# CH340.net
KiCad netlist of a schematic drawn in Altium Designer
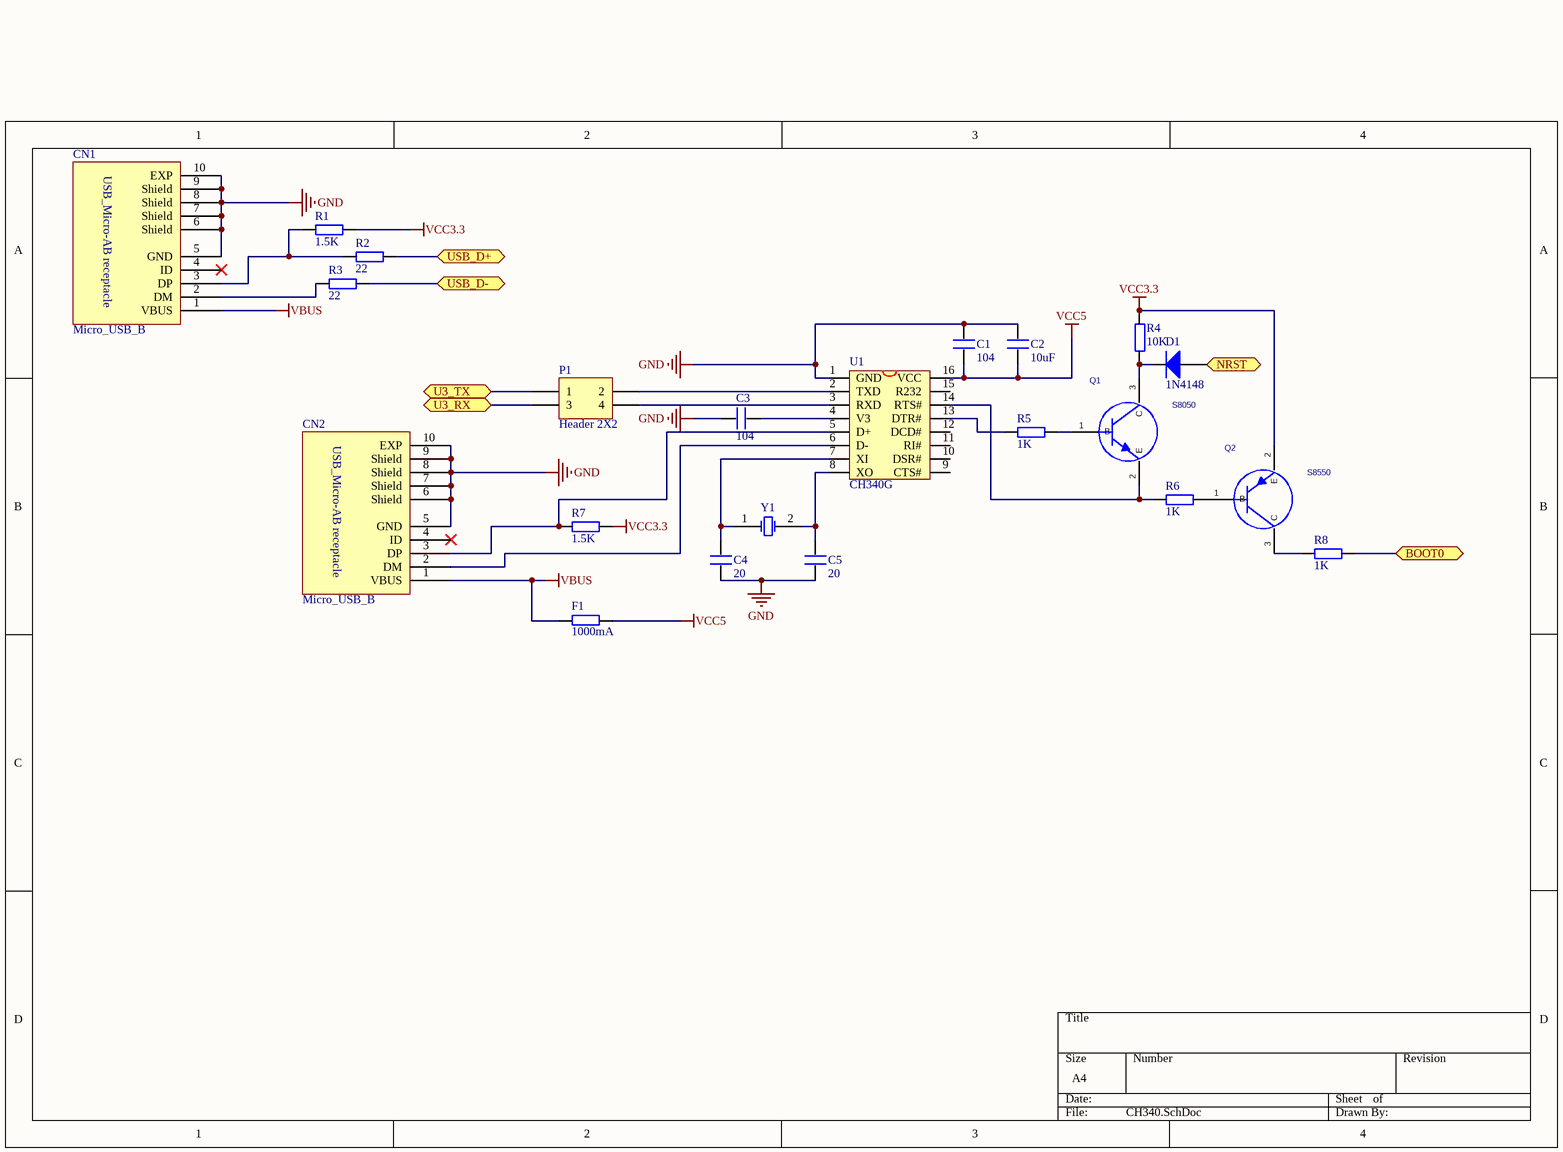
[diagram p0: CH340.SchDoc]

(export (version "E")
  (design (tool "Eeschema 10.0.6"))
  (components
    (comp (ref "C1") (value "104") (footprint "0603C") (libsource (lib "WarShip V3 STM32103封装库") (part "C")))
    (comp (ref "C2") (value "10uF") (footprint "0805C") (libsource (lib "WarShip V3 STM32103封装库") (part "C")))
    (comp (ref "C3") (value "104") (footprint "0603C") (libsource (lib "WarShip V3 STM32103封装库") (part "C")))
    (comp (ref "C4") (value "20") (footprint "0603C") (libsource (lib "WarShip V3 STM32103封装库") (part "C")))
    (comp (ref "C5") (value "20") (footprint "0603C") (libsource (lib "WarShip V3 STM32103封装库") (part "C")))
    (comp (ref "CN1")
      (value "Micro_USB_B")
      (footprint "Molex_1050170001")
      (libsource (lib "3D库") (part "Micro_USB_B"))
    )
    (comp (ref "CN2")
      (value "Micro_USB_B")
      (footprint "Molex_1050170001")
      (libsource (lib "3D库") (part "Micro_USB_B"))
    )
    (comp (ref "D1")
      (value "1N4148")
      (footprint "DIODE_SOP")
      (description "Default Diode")
      (fields (field (name "PUBLISHER") "Altium Limited"))
      (libsource (lib "3D库") (part "Diode"))
    )
    (comp (ref "F1")
      (value "1000mA")
      (footprint "0805F")
      (libsource (lib "WarShip V3 STM32103封装库") (part "R"))
    )
    (comp (ref "P1")
      (value "Header 2X2")
      (footprint "HDR2X2")
      (description "Header, 2-Pin, Dual row")
      (fields (field (name "PUBLISHER") "Altium Limited"))
      (libsource (lib "Miscellaneous Connectors") (part "Header 2X2"))
    )
    (comp (ref "Q1")
      (value "S8050")
      (footprint "SOT-23")
      (description "NPN")
      (libsource (lib "ISO-V3") (part "S8050"))
    )
    (comp (ref "Q2")
      (value "S8550")
      (footprint "SOT-23")
      (description "NPN")
      (libsource (lib "ISO-V3") (part "S8550"))
    )
    (comp (ref "R1") (value "1.5K") (footprint "0603R") (libsource (lib "Explorer STM32F407封装库") (part "R")))
    (comp (ref "R2") (value "22") (footprint "0603R") (libsource (lib "Explorer STM32F407封装库") (part "R")))
    (comp (ref "R3") (value "22") (footprint "0603R") (libsource (lib "Explorer STM32F407封装库") (part "R")))
    (comp (ref "R4") (value "10K") (footprint "0603R") (libsource (lib "Explorer STM32F407封装库") (part "R")))
    (comp (ref "R5") (value "1K") (footprint "0603R") (libsource (lib "Explorer STM32F407封装库") (part "R")))
    (comp (ref "R6") (value "1K") (footprint "0603R") (libsource (lib "Explorer STM32F407封装库") (part "R")))
    (comp (ref "R7") (value "1.5K") (footprint "0603R") (libsource (lib "Explorer STM32F407封装库") (part "R")))
    (comp (ref "R8") (value "1K") (footprint "0603R") (libsource (lib "Explorer STM32F407封装库") (part "R")))
    (comp (ref "U1")
      (value "CH340G")
      (footprint "SOP16_M")
      (description "USB2UART")
      (libsource (lib "WarShip V3 STM32103封装库") (part "CH340G"))
    )
    (comp (ref "Y1")
      (value "NX3225GD-8.000M-EXS00A-CG04874[N/A]")
      (footprint "XTAL_SMD")
      (description "Crystal Oscillator")
      (fields (field (name "PUBLISHER") "Altium Limited"))
      (libsource (lib "3D库") (part "XTAL"))
    )
  )
  (nets
    (net (code "1") (name "/BOOT0") (class "Default") (node (ref "R8") (pin "2") (pintype "passive")))
    (net (code "2") (name "/NRST") (class "Default")
      (node (ref "D1") (pin "1") (pinfunction "A_1") (pintype "passive"))
    )
    (net (code "3") (name "/U3_RX") (class "Default")
      (node (ref "P1") (pin "3") (pinfunction "3_3") (pintype "passive"))
    )
    (net (code "4") (name "/U3_TX") (class "Default")
      (node (ref "P1") (pin "1") (pinfunction "1_1") (pintype "passive"))
    )
    (net (code "5") (name "/USB_D+") (class "Default") (node (ref "R2") (pin "2") (pintype "passive")))
    (net (code "6") (name "/USB_D-") (class "Default") (node (ref "R3") (pin "2") (pintype "passive")))
    (net (code "7") (name "GND") (class "Default")
      (node (ref "C1") (pin "2") (pintype "passive"))
      (node (ref "C2") (pin "2") (pintype "passive"))
      (node (ref "C3") (pin "2") (pintype "passive"))
      (node (ref "C4") (pin "1") (pintype "passive"))
      (node (ref "C5") (pin "1") (pintype "passive"))
      (node (ref "CN1") (pin "10") (pinfunction "EXP_10") (pintype "passive"))
      (node (ref "CN1") (pin "5") (pinfunction "GND_5") (pintype "passive"))
      (node (ref "CN1") (pin "6") (pinfunction "Shield_6") (pintype "passive"))
      (node (ref "CN1") (pin "7") (pinfunction "Shield_7") (pintype "passive"))
      (node (ref "CN1") (pin "8") (pinfunction "Shield_8") (pintype "passive"))
      (node (ref "CN1") (pin "9") (pinfunction "Shield_9") (pintype "passive"))
      (node (ref "CN2") (pin "10") (pinfunction "EXP_10") (pintype "passive"))
      (node (ref "CN2") (pin "5") (pinfunction "GND_5") (pintype "passive"))
      (node (ref "CN2") (pin "6") (pinfunction "Shield_6") (pintype "passive"))
      (node (ref "CN2") (pin "7") (pinfunction "Shield_7") (pintype "passive"))
      (node (ref "CN2") (pin "8") (pinfunction "Shield_8") (pintype "passive"))
      (node (ref "CN2") (pin "9") (pinfunction "Shield_9") (pintype "passive"))
      (node (ref "U1") (pin "1") (pinfunction "GND_1") (pintype "passive"))
    )
    (net (code "8") (name "Net-(CN1-DM)") (class "Default")
      (node (ref "CN1") (pin "2") (pinfunction "DM_2") (pintype "passive"))
      (node (ref "R3") (pin "1") (pintype "passive"))
    )
    (net (code "9") (name "Net-(CN1-DP)") (class "Default")
      (node (ref "CN1") (pin "3") (pinfunction "DP_3") (pintype "passive"))
      (node (ref "R1") (pin "1") (pintype "passive"))
      (node (ref "R2") (pin "1") (pintype "passive"))
    )
    (net (code "10") (name "Net-(CN2-DM)") (class "Default")
      (node (ref "CN2") (pin "2") (pinfunction "DM_2") (pintype "passive"))
      (node (ref "U1") (pin "6") (pinfunction "D-_6") (pintype "passive"))
    )
    (net (code "11") (name "Net-(CN2-DP)") (class "Default")
      (node (ref "CN2") (pin "3") (pinfunction "DP_3") (pintype "passive"))
      (node (ref "R7") (pin "1") (pintype "passive"))
      (node (ref "U1") (pin "5") (pinfunction "D+_5") (pintype "passive"))
    )
    (net (code "12") (name "Net-(D1-K)") (class "Default")
      (node (ref "D1") (pin "2") (pinfunction "K_2") (pintype "passive"))
      (node (ref "Q1") (pin "3") (pinfunction "C_3") (pintype "passive"))
      (node (ref "R4") (pin "1") (pintype "passive"))
    )
    (net (code "13") (name "Net-(Q1-B)") (class "Default")
      (node (ref "Q1") (pin "1") (pinfunction "B_1") (pintype "passive"))
      (node (ref "R5") (pin "2") (pintype "passive"))
    )
    (net (code "14") (name "Net-(Q1-E)") (class "Default")
      (node (ref "Q1") (pin "2") (pinfunction "E_2") (pintype "passive"))
      (node (ref "R6") (pin "1") (pintype "passive"))
      (node (ref "U1") (pin "14") (pinfunction "RTS#_14") (pintype "passive"))
    )
    (net (code "15") (name "Net-(Q2-B)") (class "Default")
      (node (ref "Q2") (pin "1") (pinfunction "B_1") (pintype "passive"))
      (node (ref "R6") (pin "2") (pintype "passive"))
    )
    (net (code "16") (name "Net-(Q2-C)") (class "Default")
      (node (ref "Q2") (pin "3") (pinfunction "C_3") (pintype "passive"))
      (node (ref "R8") (pin "1") (pintype "passive"))
    )
    (net (code "17") (name "Net-(U1-DTR#)") (class "Default")
      (node (ref "R5") (pin "1") (pintype "passive"))
      (node (ref "U1") (pin "13") (pinfunction "DTR#_13") (pintype "passive"))
    )
    (net (code "18") (name "Net-(U1-RXD)") (class "Default")
      (node (ref "P1") (pin "4") (pinfunction "4_4") (pintype "passive"))
      (node (ref "U1") (pin "3") (pinfunction "RXD_3") (pintype "passive"))
    )
    (net (code "19") (name "Net-(U1-TXD)") (class "Default")
      (node (ref "P1") (pin "2") (pinfunction "2_2") (pintype "passive"))
      (node (ref "U1") (pin "2") (pinfunction "TXD_2") (pintype "passive"))
    )
    (net (code "20") (name "Net-(U1-V3)") (class "Default")
      (node (ref "C3") (pin "1") (pintype "passive"))
      (node (ref "U1") (pin "4") (pinfunction "V3_4") (pintype "passive"))
    )
    (net (code "21") (name "Net-(U1-XI)") (class "Default")
      (node (ref "C4") (pin "2") (pintype "passive"))
      (node (ref "U1") (pin "7") (pinfunction "XI_7") (pintype "passive"))
      (node (ref "Y1") (pin "1") (pinfunction "OSC1_1") (pintype "passive"))
    )
    (net (code "22") (name "Net-(U1-XO)") (class "Default")
      (node (ref "C5") (pin "2") (pintype "passive"))
      (node (ref "U1") (pin "8") (pinfunction "XO_8") (pintype "passive"))
      (node (ref "Y1") (pin "2") (pinfunction "OSC2_2") (pintype "passive"))
    )
    (net (code "23") (name "VBUS") (class "Default")
      (node (ref "CN1") (pin "1") (pinfunction "VBUS_1") (pintype "passive"))
      (node (ref "CN2") (pin "1") (pinfunction "VBUS_1") (pintype "passive"))
      (node (ref "F1") (pin "2") (pintype "passive"))
    )
    (net (code "24") (name "VCC3.3") (class "Default")
      (node (ref "Q2") (pin "2") (pinfunction "E_2") (pintype "passive"))
      (node (ref "R1") (pin "2") (pintype "passive"))
      (node (ref "R4") (pin "2") (pintype "passive"))
      (node (ref "R7") (pin "2") (pintype "passive"))
    )
    (net (code "25") (name "VCC5") (class "Default")
      (node (ref "C1") (pin "1") (pintype "passive"))
      (node (ref "C2") (pin "1") (pintype "passive"))
      (node (ref "F1") (pin "1") (pintype "passive"))
      (node (ref "U1") (pin "16") (pinfunction "VCC_16") (pintype "passive"))
    )
    (net (code "26") (name "unconnected-(CN1-ID-Pad4)") (class "Default")
      (node (ref "CN1") (pin "4") (pinfunction "ID_4") (pintype "passive+no_connect"))
    )
    (net (code "27") (name "unconnected-(CN2-ID-Pad4)") (class "Default")
      (node (ref "CN2") (pin "4") (pinfunction "ID_4") (pintype "passive+no_connect"))
    )
    (net (code "28") (name "unconnected-(U1-CTS#-Pad9)") (class "Default")
      (node (ref "U1") (pin "9") (pinfunction "CTS#_9") (pintype "passive"))
    )
    (net (code "29") (name "unconnected-(U1-DCD#-Pad12)") (class "Default")
      (node (ref "U1") (pin "12") (pinfunction "DCD#_12") (pintype "passive"))
    )
    (net (code "30") (name "unconnected-(U1-DSR#-Pad10)") (class "Default")
      (node (ref "U1") (pin "10") (pinfunction "DSR#_10") (pintype "passive"))
    )
    (net (code "31") (name "unconnected-(U1-R232-Pad15)") (class "Default")
      (node (ref "U1") (pin "15") (pinfunction "R232_15") (pintype "passive"))
    )
    (net (code "32") (name "unconnected-(U1-RI#-Pad11)") (class "Default")
      (node (ref "U1") (pin "11") (pinfunction "RI#_11") (pintype "passive"))
    )
  )
)
